# CurvedThumbs.net
KiCad netlist of a schematic drawn in EAGLE
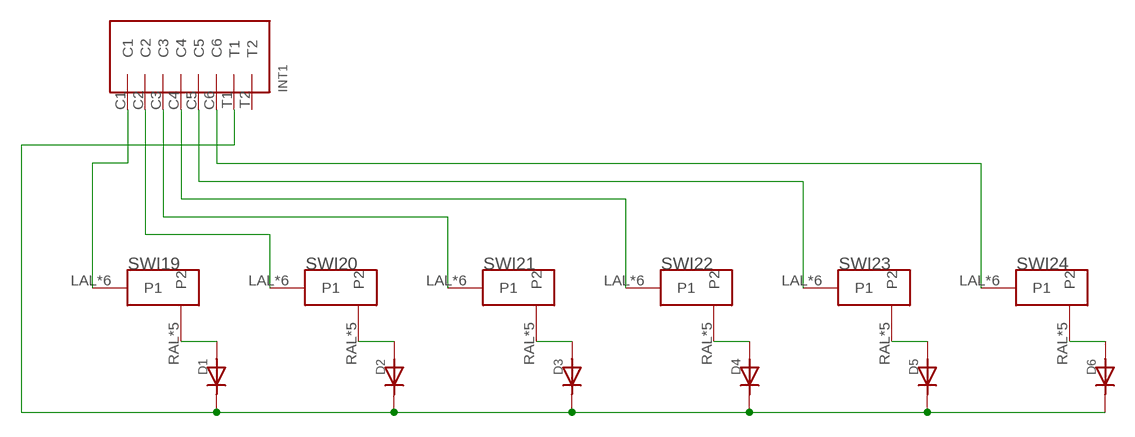
[diagram p0: schematic, sheet 1]

(export (version "E")
  (design (tool "Eeschema 10.0.6"))
  (components
    (comp (ref "D1")
      (value "DIODE")
      (footprint "eagle-import:DIODE_COMBO")
      (libsource (lib "eagle-import") (part "DIODE"))
    )
    (comp (ref "D2")
      (value "DIODE")
      (footprint "eagle-import:DIODE_COMBO")
      (libsource (lib "eagle-import") (part "DIODE"))
    )
    (comp (ref "D3")
      (value "DIODE")
      (footprint "eagle-import:DIODE_COMBO")
      (libsource (lib "eagle-import") (part "DIODE"))
    )
    (comp (ref "D4")
      (value "DIODE")
      (footprint "eagle-import:DIODE_COMBO")
      (libsource (lib "eagle-import") (part "DIODE"))
    )
    (comp (ref "D5")
      (value "DIODE")
      (footprint "eagle-import:DIODE_COMBO")
      (libsource (lib "eagle-import") (part "DIODE"))
    )
    (comp (ref "D6")
      (value "DIODE")
      (footprint "eagle-import:DIODE_COMBO")
      (libsource (lib "eagle-import") (part "DIODE"))
    )
    (comp (ref "INT1")
      (value "INTRCNNT4X2")
      (footprint "eagle-import:INTRRIBBON")
      (libsource (lib "eagle-import") (part "INTRCNNT4X2"))
    )
    (comp (ref "SWI19")
      (value "MX/ALPSDOUBLESIDED")
      (footprint "eagle-import:DOUBLED_MX_ALPS")
      (libsource (lib "eagle-import") (part "MX/ALPSDOUBLESIDED"))
    )
    (comp (ref "SWI20")
      (value "MX/ALPSDOUBLESIDED")
      (footprint "eagle-import:DOUBLED_MX_ALPS")
      (libsource (lib "eagle-import") (part "MX/ALPSDOUBLESIDED"))
    )
    (comp (ref "SWI21")
      (value "MX/ALPSDOUBLESIDED")
      (footprint "eagle-import:DOUBLED_MX_ALPS")
      (libsource (lib "eagle-import") (part "MX/ALPSDOUBLESIDED"))
    )
    (comp (ref "SWI22")
      (value "MX/ALPSDOUBLESIDED")
      (footprint "eagle-import:DOUBLED_MX_ALPS")
      (libsource (lib "eagle-import") (part "MX/ALPSDOUBLESIDED"))
    )
    (comp (ref "SWI23")
      (value "MX/ALPSDOUBLESIDED")
      (footprint "eagle-import:DOUBLED_MX_ALPS")
      (libsource (lib "eagle-import") (part "MX/ALPSDOUBLESIDED"))
    )
    (comp (ref "SWI24")
      (value "MX/ALPSDOUBLESIDED")
      (footprint "eagle-import:DOUBLED_MX_ALPS")
      (libsource (lib "eagle-import") (part "MX/ALPSDOUBLESIDED"))
    )
  )
  (nets
    (net (code "1") (name "Net-(D1-AN-PadANOSB)") (class "Default")
      (node (ref "D1") (pin "ANOSB") (pinfunction "AN_ANOSB") (pintype "bidirectional"))
      (node (ref "D1") (pin "ANOST") (pinfunction "AN_ANOST") (pintype "bidirectional"))
      (node (ref "D1") (pin "ANOT") (pinfunction "AN_ANOT") (pintype "bidirectional"))
      (node (ref "SWI19") (pin "RAL") (pinfunction "P2_RAL") (pintype "bidirectional"))
      (node (ref "SWI19") (pin "RAR") (pinfunction "P2_RAR") (pintype "bidirectional"))
      (node (ref "SWI19") (pin "RCL") (pinfunction "P2_RCL") (pintype "bidirectional"))
      (node (ref "SWI19") (pin "RCR") (pinfunction "P2_RCR") (pintype "bidirectional"))
      (node (ref "SWI19") (pin "RLMID") (pinfunction "P2_RLMID") (pintype "bidirectional"))
    )
    (net (code "2") (name "Net-(D1-CAT-PadCATSB)") (class "Default")
      (node (ref "D1") (pin "CATSB") (pinfunction "CAT_CATSB") (pintype "bidirectional"))
      (node (ref "D1") (pin "CATST") (pinfunction "CAT_CATST") (pintype "bidirectional"))
      (node (ref "D1") (pin "CATT") (pinfunction "CAT_CATT") (pintype "bidirectional"))
      (node (ref "D2") (pin "CATSB") (pinfunction "CAT_CATSB") (pintype "bidirectional"))
      (node (ref "D2") (pin "CATST") (pinfunction "CAT_CATST") (pintype "bidirectional"))
      (node (ref "D2") (pin "CATT") (pinfunction "CAT_CATT") (pintype "bidirectional"))
      (node (ref "D3") (pin "CATSB") (pinfunction "CAT_CATSB") (pintype "bidirectional"))
      (node (ref "D3") (pin "CATST") (pinfunction "CAT_CATST") (pintype "bidirectional"))
      (node (ref "D3") (pin "CATT") (pinfunction "CAT_CATT") (pintype "bidirectional"))
      (node (ref "D4") (pin "CATSB") (pinfunction "CAT_CATSB") (pintype "bidirectional"))
      (node (ref "D4") (pin "CATST") (pinfunction "CAT_CATST") (pintype "bidirectional"))
      (node (ref "D4") (pin "CATT") (pinfunction "CAT_CATT") (pintype "bidirectional"))
      (node (ref "D5") (pin "CATSB") (pinfunction "CAT_CATSB") (pintype "bidirectional"))
      (node (ref "D5") (pin "CATST") (pinfunction "CAT_CATST") (pintype "bidirectional"))
      (node (ref "D5") (pin "CATT") (pinfunction "CAT_CATT") (pintype "bidirectional"))
      (node (ref "D6") (pin "CATSB") (pinfunction "CAT_CATSB") (pintype "bidirectional"))
      (node (ref "D6") (pin "CATST") (pinfunction "CAT_CATST") (pintype "bidirectional"))
      (node (ref "D6") (pin "CATT") (pinfunction "CAT_CATT") (pintype "bidirectional"))
      (node (ref "INT1") (pin "T1") (pinfunction "T1_T1") (pintype "bidirectional"))
    )
    (net (code "3") (name "Net-(D2-AN-PadANOSB)") (class "Default")
      (node (ref "D2") (pin "ANOSB") (pinfunction "AN_ANOSB") (pintype "bidirectional"))
      (node (ref "D2") (pin "ANOST") (pinfunction "AN_ANOST") (pintype "bidirectional"))
      (node (ref "D2") (pin "ANOT") (pinfunction "AN_ANOT") (pintype "bidirectional"))
      (node (ref "SWI20") (pin "RAL") (pinfunction "P2_RAL") (pintype "bidirectional"))
      (node (ref "SWI20") (pin "RAR") (pinfunction "P2_RAR") (pintype "bidirectional"))
      (node (ref "SWI20") (pin "RCL") (pinfunction "P2_RCL") (pintype "bidirectional"))
      (node (ref "SWI20") (pin "RCR") (pinfunction "P2_RCR") (pintype "bidirectional"))
      (node (ref "SWI20") (pin "RLMID") (pinfunction "P2_RLMID") (pintype "bidirectional"))
    )
    (net (code "4") (name "Net-(D3-AN-PadANOSB)") (class "Default")
      (node (ref "D3") (pin "ANOSB") (pinfunction "AN_ANOSB") (pintype "bidirectional"))
      (node (ref "D3") (pin "ANOST") (pinfunction "AN_ANOST") (pintype "bidirectional"))
      (node (ref "D3") (pin "ANOT") (pinfunction "AN_ANOT") (pintype "bidirectional"))
      (node (ref "SWI21") (pin "RAL") (pinfunction "P2_RAL") (pintype "bidirectional"))
      (node (ref "SWI21") (pin "RAR") (pinfunction "P2_RAR") (pintype "bidirectional"))
      (node (ref "SWI21") (pin "RCL") (pinfunction "P2_RCL") (pintype "bidirectional"))
      (node (ref "SWI21") (pin "RCR") (pinfunction "P2_RCR") (pintype "bidirectional"))
      (node (ref "SWI21") (pin "RLMID") (pinfunction "P2_RLMID") (pintype "bidirectional"))
    )
    (net (code "5") (name "Net-(D4-AN-PadANOSB)") (class "Default")
      (node (ref "D4") (pin "ANOSB") (pinfunction "AN_ANOSB") (pintype "bidirectional"))
      (node (ref "D4") (pin "ANOST") (pinfunction "AN_ANOST") (pintype "bidirectional"))
      (node (ref "D4") (pin "ANOT") (pinfunction "AN_ANOT") (pintype "bidirectional"))
      (node (ref "SWI22") (pin "RAL") (pinfunction "P2_RAL") (pintype "bidirectional"))
      (node (ref "SWI22") (pin "RAR") (pinfunction "P2_RAR") (pintype "bidirectional"))
      (node (ref "SWI22") (pin "RCL") (pinfunction "P2_RCL") (pintype "bidirectional"))
      (node (ref "SWI22") (pin "RCR") (pinfunction "P2_RCR") (pintype "bidirectional"))
      (node (ref "SWI22") (pin "RLMID") (pinfunction "P2_RLMID") (pintype "bidirectional"))
    )
    (net (code "6") (name "Net-(D5-AN-PadANOSB)") (class "Default")
      (node (ref "D5") (pin "ANOSB") (pinfunction "AN_ANOSB") (pintype "bidirectional"))
      (node (ref "D5") (pin "ANOST") (pinfunction "AN_ANOST") (pintype "bidirectional"))
      (node (ref "D5") (pin "ANOT") (pinfunction "AN_ANOT") (pintype "bidirectional"))
      (node (ref "SWI23") (pin "RAL") (pinfunction "P2_RAL") (pintype "bidirectional"))
      (node (ref "SWI23") (pin "RAR") (pinfunction "P2_RAR") (pintype "bidirectional"))
      (node (ref "SWI23") (pin "RCL") (pinfunction "P2_RCL") (pintype "bidirectional"))
      (node (ref "SWI23") (pin "RCR") (pinfunction "P2_RCR") (pintype "bidirectional"))
      (node (ref "SWI23") (pin "RLMID") (pinfunction "P2_RLMID") (pintype "bidirectional"))
    )
    (net (code "7") (name "Net-(D6-AN-PadANOSB)") (class "Default")
      (node (ref "D6") (pin "ANOSB") (pinfunction "AN_ANOSB") (pintype "bidirectional"))
      (node (ref "D6") (pin "ANOST") (pinfunction "AN_ANOST") (pintype "bidirectional"))
      (node (ref "D6") (pin "ANOT") (pinfunction "AN_ANOT") (pintype "bidirectional"))
      (node (ref "SWI24") (pin "RAL") (pinfunction "P2_RAL") (pintype "bidirectional"))
      (node (ref "SWI24") (pin "RAR") (pinfunction "P2_RAR") (pintype "bidirectional"))
      (node (ref "SWI24") (pin "RCL") (pinfunction "P2_RCL") (pintype "bidirectional"))
      (node (ref "SWI24") (pin "RCR") (pinfunction "P2_RCR") (pintype "bidirectional"))
      (node (ref "SWI24") (pin "RLMID") (pinfunction "P2_RLMID") (pintype "bidirectional"))
    )
    (net (code "8") (name "Net-(INT1-PadC1)") (class "Default")
      (node (ref "INT1") (pin "C1") (pinfunction "C1_C1") (pintype "bidirectional"))
      (node (ref "SWI19") (pin "LAL") (pinfunction "P1_LAL") (pintype "bidirectional"))
      (node (ref "SWI19") (pin "LAR") (pinfunction "P1_LAR") (pintype "bidirectional"))
      (node (ref "SWI19") (pin "LCL") (pinfunction "P1_LCL") (pintype "bidirectional"))
      (node (ref "SWI19") (pin "LCR") (pinfunction "P1_LCR") (pintype "bidirectional"))
      (node (ref "SWI19") (pin "LLP") (pinfunction "P1_LLP") (pintype "bidirectional"))
      (node (ref "SWI19") (pin "LRLP") (pinfunction "P1_LRLP") (pintype "bidirectional"))
    )
    (net (code "9") (name "Net-(INT1-PadC2)") (class "Default")
      (node (ref "INT1") (pin "C2") (pinfunction "C2_C2") (pintype "bidirectional"))
      (node (ref "SWI20") (pin "LAL") (pinfunction "P1_LAL") (pintype "bidirectional"))
      (node (ref "SWI20") (pin "LAR") (pinfunction "P1_LAR") (pintype "bidirectional"))
      (node (ref "SWI20") (pin "LCL") (pinfunction "P1_LCL") (pintype "bidirectional"))
      (node (ref "SWI20") (pin "LCR") (pinfunction "P1_LCR") (pintype "bidirectional"))
      (node (ref "SWI20") (pin "LLP") (pinfunction "P1_LLP") (pintype "bidirectional"))
      (node (ref "SWI20") (pin "LRLP") (pinfunction "P1_LRLP") (pintype "bidirectional"))
    )
    (net (code "10") (name "Net-(INT1-PadC3)") (class "Default")
      (node (ref "INT1") (pin "C3") (pinfunction "C3_C3") (pintype "bidirectional"))
      (node (ref "SWI21") (pin "LAL") (pinfunction "P1_LAL") (pintype "bidirectional"))
      (node (ref "SWI21") (pin "LAR") (pinfunction "P1_LAR") (pintype "bidirectional"))
      (node (ref "SWI21") (pin "LCL") (pinfunction "P1_LCL") (pintype "bidirectional"))
      (node (ref "SWI21") (pin "LCR") (pinfunction "P1_LCR") (pintype "bidirectional"))
      (node (ref "SWI21") (pin "LLP") (pinfunction "P1_LLP") (pintype "bidirectional"))
      (node (ref "SWI21") (pin "LRLP") (pinfunction "P1_LRLP") (pintype "bidirectional"))
    )
    (net (code "11") (name "Net-(INT1-PadC4)") (class "Default")
      (node (ref "INT1") (pin "C4") (pinfunction "C4_C4") (pintype "bidirectional"))
      (node (ref "SWI22") (pin "LAL") (pinfunction "P1_LAL") (pintype "bidirectional"))
      (node (ref "SWI22") (pin "LAR") (pinfunction "P1_LAR") (pintype "bidirectional"))
      (node (ref "SWI22") (pin "LCL") (pinfunction "P1_LCL") (pintype "bidirectional"))
      (node (ref "SWI22") (pin "LCR") (pinfunction "P1_LCR") (pintype "bidirectional"))
      (node (ref "SWI22") (pin "LLP") (pinfunction "P1_LLP") (pintype "bidirectional"))
      (node (ref "SWI22") (pin "LRLP") (pinfunction "P1_LRLP") (pintype "bidirectional"))
    )
    (net (code "12") (name "Net-(INT1-PadC5)") (class "Default")
      (node (ref "INT1") (pin "C5") (pinfunction "C5_C5") (pintype "bidirectional"))
      (node (ref "SWI23") (pin "LAL") (pinfunction "P1_LAL") (pintype "bidirectional"))
      (node (ref "SWI23") (pin "LAR") (pinfunction "P1_LAR") (pintype "bidirectional"))
      (node (ref "SWI23") (pin "LCL") (pinfunction "P1_LCL") (pintype "bidirectional"))
      (node (ref "SWI23") (pin "LCR") (pinfunction "P1_LCR") (pintype "bidirectional"))
      (node (ref "SWI23") (pin "LLP") (pinfunction "P1_LLP") (pintype "bidirectional"))
      (node (ref "SWI23") (pin "LRLP") (pinfunction "P1_LRLP") (pintype "bidirectional"))
    )
    (net (code "13") (name "Net-(INT1-PadC6)") (class "Default")
      (node (ref "INT1") (pin "C6") (pinfunction "C6_C6") (pintype "bidirectional"))
      (node (ref "SWI24") (pin "LAL") (pinfunction "P1_LAL") (pintype "bidirectional"))
      (node (ref "SWI24") (pin "LAR") (pinfunction "P1_LAR") (pintype "bidirectional"))
      (node (ref "SWI24") (pin "LCL") (pinfunction "P1_LCL") (pintype "bidirectional"))
      (node (ref "SWI24") (pin "LCR") (pinfunction "P1_LCR") (pintype "bidirectional"))
      (node (ref "SWI24") (pin "LLP") (pinfunction "P1_LLP") (pintype "bidirectional"))
      (node (ref "SWI24") (pin "LRLP") (pinfunction "P1_LRLP") (pintype "bidirectional"))
    )
    (net (code "14") (name "unconnected-(INT1-PadT2)") (class "Default")
      (node (ref "INT1") (pin "T2") (pinfunction "T2_T2") (pintype "bidirectional"))
    )
  )
)
